# SimulatorT2SecondPCRevA.net
KiCad netlist of a schematic drawn in EAGLE
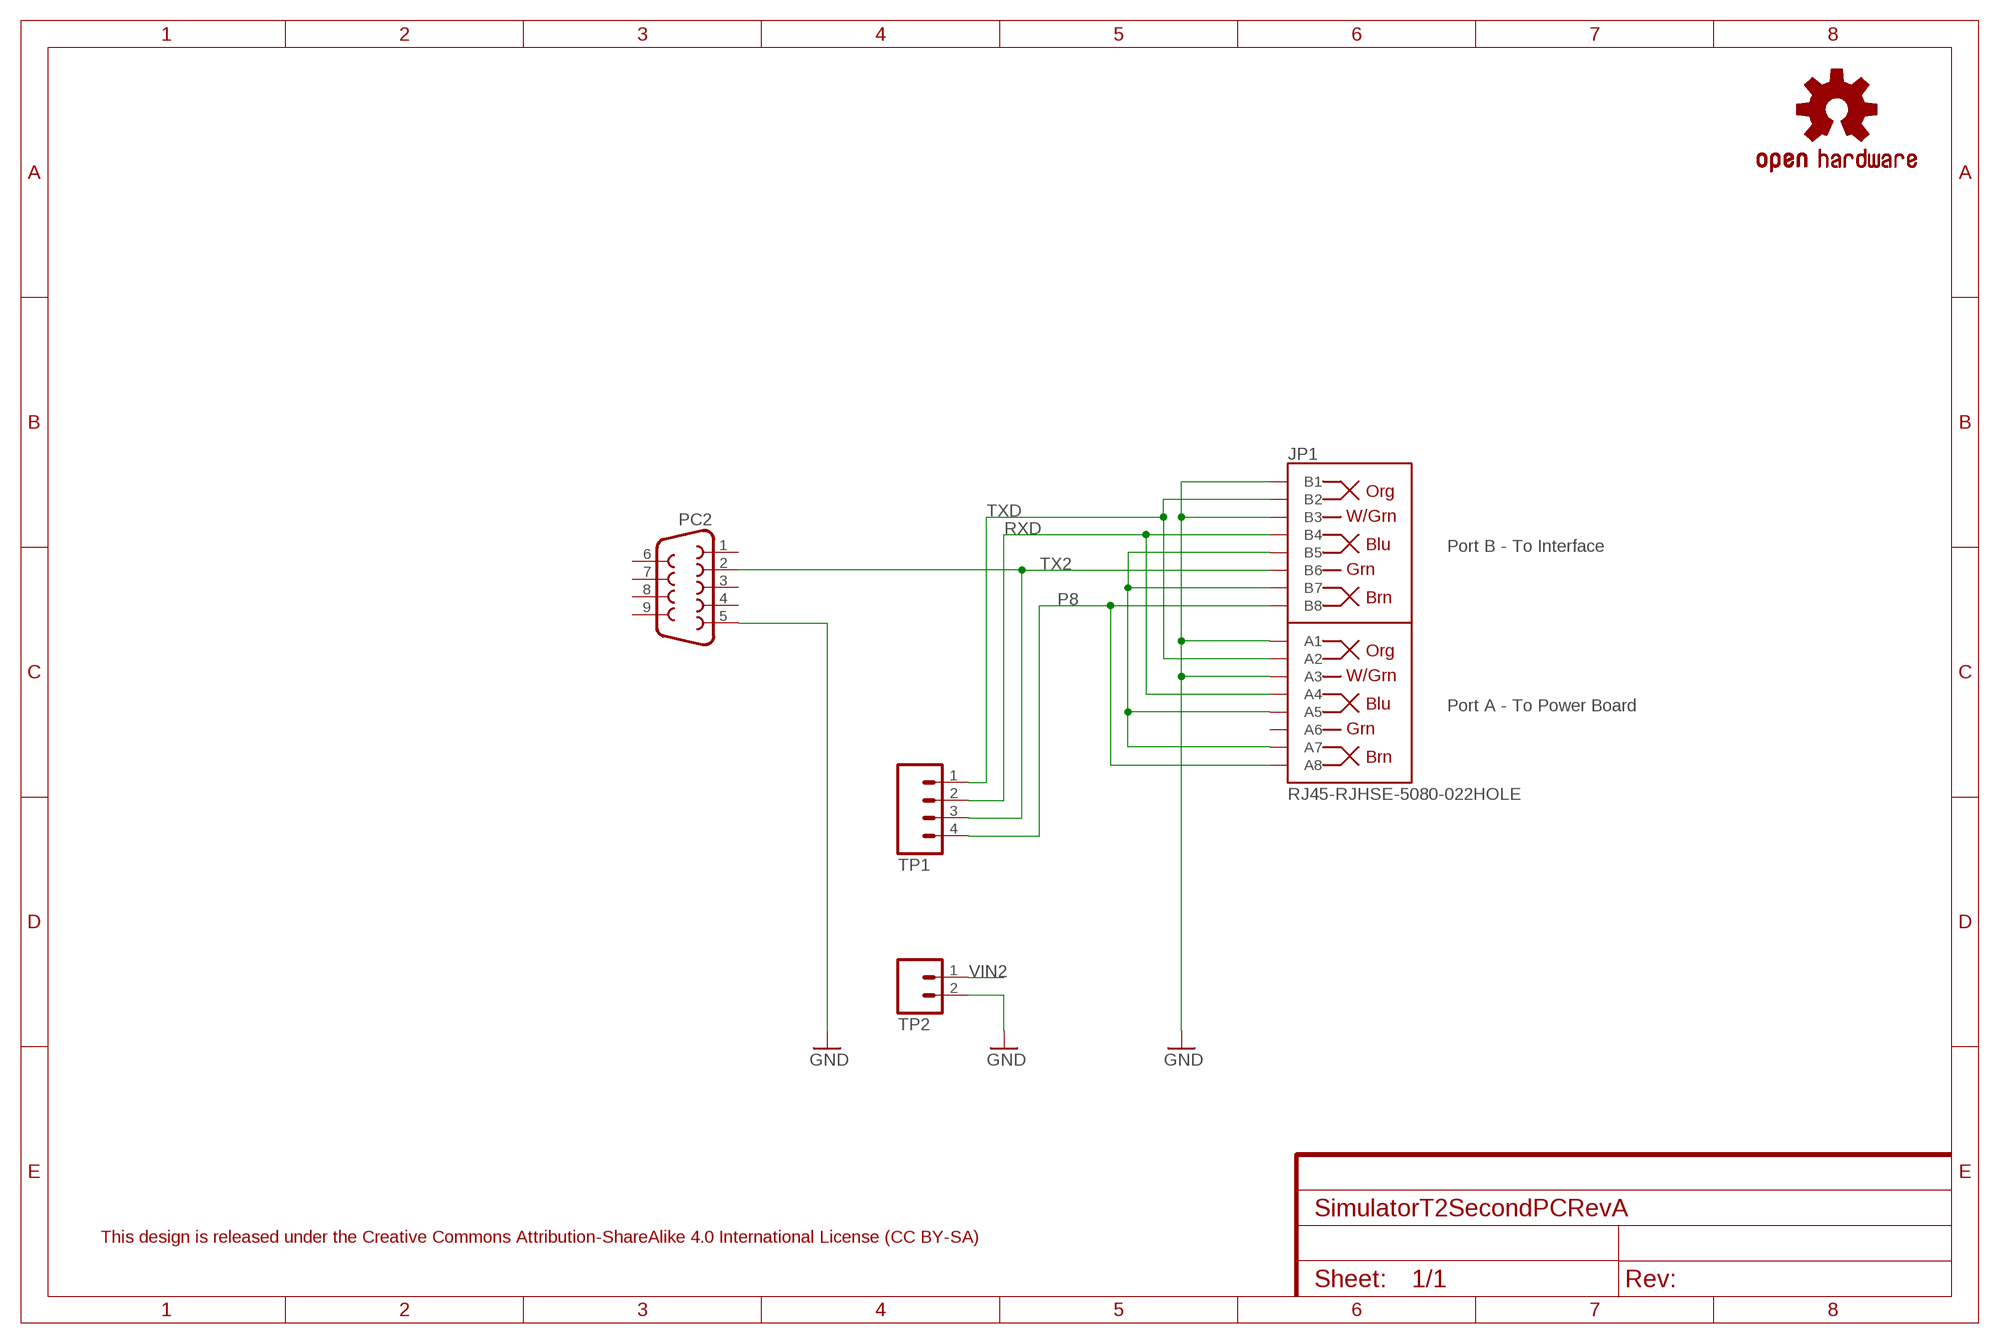
[diagram p0: schematic, sheet 1]

(export (version "E")
  (design (tool "Eeschema 10.0.6"))
  (components
    (comp (ref "JP1")
      (value "RJ45-RJHSE-5080-022HOLE")
      (footprint "eagle-import:RJ45-RJHSE-5080-02")
      (libsource (lib "eagle-import") (part "RJ45-RJHSE-5080-022HOLE"))
    )
    (comp (ref "LOGO1")
      (value "OSHW-LOGOS")
      (footprint "eagle-import:OSHW-LOGO-S")
      (libsource (lib "eagle-import") (part "OSHW-LOGOS"))
    )
    (comp (ref "PC2")
      (value "DB9-CONNECTOR-PCBFEMALE")
      (footprint "eagle-import:MULTICOMP-DB9-FEMALE-PCB-90DEG")
      (libsource (lib "eagle-import") (part "DB9-CONNECTOR-PCBFEMALE"))
    )
    (comp (ref "TP1")
      (value "M04PTH")
      (footprint "eagle-import:1X04")
      (libsource (lib "eagle-import") (part "M04PTH"))
    )
    (comp (ref "TP2")
      (value "M02PTH")
      (footprint "eagle-import:1X02")
      (libsource (lib "eagle-import") (part "M02PTH"))
    )
  )
  (nets
    (net (code "1") (name "/P8") (class "Default")
      (node (ref "JP1") (pin "A8") (pinfunction "A8_A8") (pintype "bidirectional"))
      (node (ref "JP1") (pin "B8") (pinfunction "B8_B8") (pintype "bidirectional"))
      (node (ref "TP1") (pin "4") (pinfunction "4_4") (pintype "passive"))
    )
    (net (code "2") (name "/RXD") (class "Default")
      (node (ref "JP1") (pin "A4") (pinfunction "A4_A4") (pintype "bidirectional"))
      (node (ref "JP1") (pin "B4") (pinfunction "B4_B4") (pintype "bidirectional"))
      (node (ref "TP1") (pin "2") (pinfunction "2_2") (pintype "passive"))
    )
    (net (code "3") (name "/TX2") (class "Default")
      (node (ref "JP1") (pin "B6") (pinfunction "B6_B6") (pintype "bidirectional"))
      (node (ref "PC2") (pin "2") (pinfunction "2_2") (pintype "passive"))
      (node (ref "TP1") (pin "3") (pinfunction "3_3") (pintype "passive"))
    )
    (net (code "4") (name "/TXD") (class "Default")
      (node (ref "JP1") (pin "A2") (pinfunction "A2_A2") (pintype "bidirectional"))
      (node (ref "JP1") (pin "B2") (pinfunction "B2_B2") (pintype "bidirectional"))
      (node (ref "TP1") (pin "1") (pinfunction "1_1") (pintype "passive"))
    )
    (net (code "5") (name "/VIN2") (class "Default")
      (node (ref "JP1") (pin "A5") (pinfunction "A5_A5") (pintype "bidirectional"))
      (node (ref "JP1") (pin "A7") (pinfunction "A7_A7") (pintype "bidirectional"))
      (node (ref "JP1") (pin "B5") (pinfunction "B5_B5") (pintype "bidirectional"))
      (node (ref "JP1") (pin "B7") (pinfunction "B7_B7") (pintype "bidirectional"))
      (node (ref "TP2") (pin "1") (pinfunction "1_1") (pintype "passive"))
    )
    (net (code "6") (name "GND") (class "Default")
      (node (ref "JP1") (pin "A1") (pinfunction "A1_A1") (pintype "bidirectional"))
      (node (ref "JP1") (pin "A3") (pinfunction "A3_A3") (pintype "bidirectional"))
      (node (ref "JP1") (pin "B1") (pinfunction "B1_B1") (pintype "bidirectional"))
      (node (ref "JP1") (pin "B3") (pinfunction "B3_B3") (pintype "bidirectional"))
      (node (ref "PC2") (pin "5") (pinfunction "5_5") (pintype "passive"))
      (node (ref "TP2") (pin "2") (pinfunction "2_2") (pintype "passive"))
    )
    (net (code "7") (name "unconnected-(JP1-PadA6)") (class "Default")
      (node (ref "JP1") (pin "A6") (pinfunction "A6_A6") (pintype "bidirectional"))
    )
    (net (code "8") (name "unconnected-(PC2-Pad1)") (class "Default")
      (node (ref "PC2") (pin "1") (pinfunction "1_1") (pintype "passive"))
    )
    (net (code "9") (name "unconnected-(PC2-Pad3)") (class "Default")
      (node (ref "PC2") (pin "3") (pinfunction "3_3") (pintype "passive"))
    )
    (net (code "10") (name "unconnected-(PC2-Pad4)") (class "Default")
      (node (ref "PC2") (pin "4") (pinfunction "4_4") (pintype "passive"))
    )
    (net (code "11") (name "unconnected-(PC2-Pad6)") (class "Default")
      (node (ref "PC2") (pin "6") (pinfunction "6_6") (pintype "passive"))
    )
    (net (code "12") (name "unconnected-(PC2-Pad7)") (class "Default")
      (node (ref "PC2") (pin "7") (pinfunction "7_7") (pintype "passive"))
    )
    (net (code "13") (name "unconnected-(PC2-Pad8)") (class "Default")
      (node (ref "PC2") (pin "8") (pinfunction "8_8") (pintype "passive"))
    )
    (net (code "14") (name "unconnected-(PC2-Pad9)") (class "Default")
      (node (ref "PC2") (pin "9") (pinfunction "9_9") (pintype "passive"))
    )
  )
)
